# hat.net
KiCad netlist of a schematic drawn in EAGLE
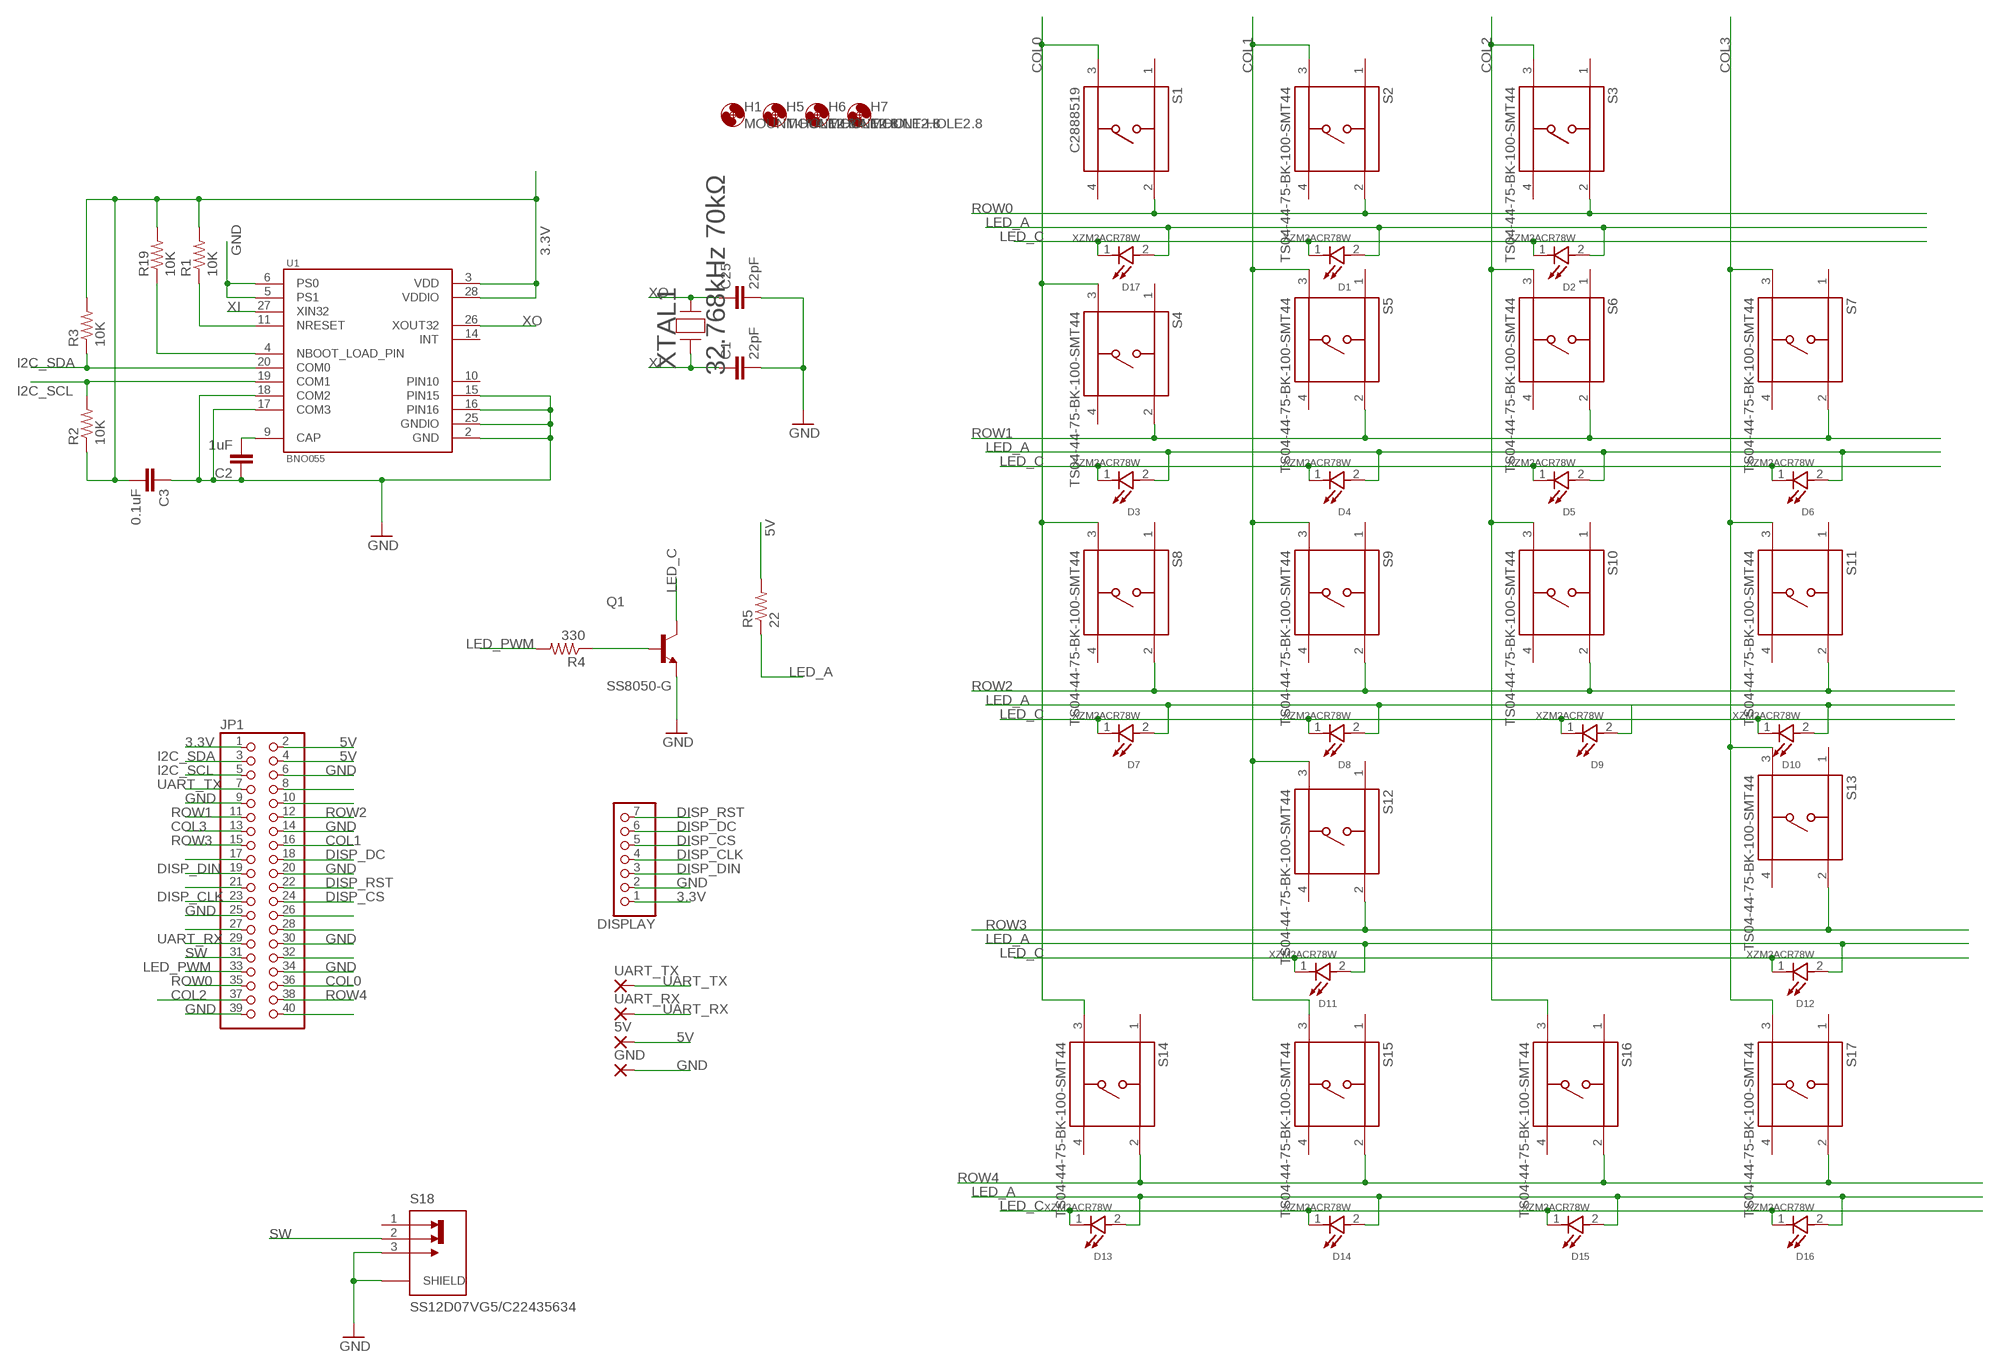
[diagram p0: schematic, sheet 1]

(export (version "E")
  (design (tool "Eeschema 10.0.6"))
  (components
    (comp (ref "5V")
      (value "SMD2")
      (footprint "eagle-import:SMD1,27-2,54")
      (libsource (lib "eagle-import") (part "SMD2"))
    )
    (comp (ref "C1")
      (value "22pF")
      (footprint "eagle-import:CAP_0603")
      (fields
        (field (name "DIGIKEY_PART_NUMBER") "399-7814-2-ND")
        (field (name "MANUFACTURER") "KEMET")
        (field (name "MPN") "C0603C100C5GACTU")
        (field (name "CREATED_BY") "PCBLayout.com")
      )
      (libsource (lib "eagle-import") (part "C0603C100C5GACTU"))
    )
    (comp (ref "C2")
      (value "1uF")
      (footprint "eagle-import:CAP_0603")
      (fields
        (field (name "DIGIKEY_PART_NUMBER") "399-7814-2-ND")
        (field (name "MANUFACTURER") "KEMET")
        (field (name "MPN") "C0603C100C5GACTU")
        (field (name "CREATED_BY") "PCBLayout.com")
      )
      (libsource (lib "eagle-import") (part "C0603C100C5GACTU"))
    )
    (comp (ref "C3")
      (value "0.1uF")
      (footprint "eagle-import:CAP_0603")
      (fields
        (field (name "DIGIKEY_PART_NUMBER") "399-7814-2-ND")
        (field (name "MANUFACTURER") "KEMET")
        (field (name "MPN") "C0603C100C5GACTU")
        (field (name "CREATED_BY") "PCBLayout.com")
      )
      (libsource (lib "eagle-import") (part "C0603C100C5GACTU"))
    )
    (comp (ref "C25")
      (value "22pF")
      (footprint "eagle-import:CAP_0603")
      (fields
        (field (name "DIGIKEY_PART_NUMBER") "399-7814-2-ND")
        (field (name "MANUFACTURER") "KEMET")
        (field (name "MPN") "C0603C100C5GACTU")
        (field (name "CREATED_BY") "PCBLayout.com")
      )
      (libsource (lib "eagle-import") (part "C0603C100C5GACTU"))
    )
    (comp (ref "D1")
      (value "XZM2ACR78W")
      (footprint "eagle-import:LED_XZM2ACR78W")
      (fields (field (name "MF") "SunLED"))
      (libsource (lib "eagle-import") (part "XZM2ACR78W"))
    )
    (comp (ref "D2")
      (value "XZM2ACR78W")
      (footprint "eagle-import:LED_XZM2ACR78W")
      (fields (field (name "MF") "SunLED"))
      (libsource (lib "eagle-import") (part "XZM2ACR78W"))
    )
    (comp (ref "D3")
      (value "XZM2ACR78W")
      (footprint "eagle-import:LED_XZM2ACR78W")
      (fields (field (name "MF") "SunLED"))
      (libsource (lib "eagle-import") (part "XZM2ACR78W"))
    )
    (comp (ref "D4")
      (value "XZM2ACR78W")
      (footprint "eagle-import:LED_XZM2ACR78W")
      (fields (field (name "MF") "SunLED"))
      (libsource (lib "eagle-import") (part "XZM2ACR78W"))
    )
    (comp (ref "D5")
      (value "XZM2ACR78W")
      (footprint "eagle-import:LED_XZM2ACR78W")
      (fields (field (name "MF") "SunLED"))
      (libsource (lib "eagle-import") (part "XZM2ACR78W"))
    )
    (comp (ref "D6")
      (value "XZM2ACR78W")
      (footprint "eagle-import:LED_XZM2ACR78W")
      (fields (field (name "MF") "SunLED"))
      (libsource (lib "eagle-import") (part "XZM2ACR78W"))
    )
    (comp (ref "D7")
      (value "XZM2ACR78W")
      (footprint "eagle-import:LED_XZM2ACR78W")
      (fields (field (name "MF") "SunLED"))
      (libsource (lib "eagle-import") (part "XZM2ACR78W"))
    )
    (comp (ref "D8")
      (value "XZM2ACR78W")
      (footprint "eagle-import:LED_XZM2ACR78W")
      (fields (field (name "MF") "SunLED"))
      (libsource (lib "eagle-import") (part "XZM2ACR78W"))
    )
    (comp (ref "D9")
      (value "XZM2ACR78W")
      (footprint "eagle-import:LED_XZM2ACR78W")
      (fields (field (name "MF") "SunLED"))
      (libsource (lib "eagle-import") (part "XZM2ACR78W"))
    )
    (comp (ref "D10")
      (value "XZM2ACR78W")
      (footprint "eagle-import:LED_XZM2ACR78W")
      (fields (field (name "MF") "SunLED"))
      (libsource (lib "eagle-import") (part "XZM2ACR78W"))
    )
    (comp (ref "D11")
      (value "XZM2ACR78W")
      (footprint "eagle-import:LED_XZM2ACR78W")
      (fields (field (name "MF") "SunLED"))
      (libsource (lib "eagle-import") (part "XZM2ACR78W"))
    )
    (comp (ref "D12")
      (value "XZM2ACR78W")
      (footprint "eagle-import:LED_XZM2ACR78W")
      (fields (field (name "MF") "SunLED"))
      (libsource (lib "eagle-import") (part "XZM2ACR78W"))
    )
    (comp (ref "D13")
      (value "XZM2ACR78W")
      (footprint "eagle-import:LED_XZM2ACR78W")
      (fields (field (name "MF") "SunLED"))
      (libsource (lib "eagle-import") (part "XZM2ACR78W"))
    )
    (comp (ref "D14")
      (value "XZM2ACR78W")
      (footprint "eagle-import:LED_XZM2ACR78W")
      (fields (field (name "MF") "SunLED"))
      (libsource (lib "eagle-import") (part "XZM2ACR78W"))
    )
    (comp (ref "D15")
      (value "XZM2ACR78W")
      (footprint "eagle-import:LED_XZM2ACR78W")
      (fields (field (name "MF") "SunLED"))
      (libsource (lib "eagle-import") (part "XZM2ACR78W"))
    )
    (comp (ref "D16")
      (value "XZM2ACR78W")
      (footprint "eagle-import:LED_XZM2ACR78W")
      (fields (field (name "MF") "SunLED"))
      (libsource (lib "eagle-import") (part "XZM2ACR78W"))
    )
    (comp (ref "D17")
      (value "XZM2ACR78W")
      (footprint "eagle-import:LED_XZM2ACR78W")
      (fields (field (name "MF") "SunLED"))
      (libsource (lib "eagle-import") (part "XZM2ACR78W"))
    )
    (comp (ref "DISPLAY")
      (value "PINHD-1X7")
      (footprint "eagle-import:1X07")
      (libsource (lib "eagle-import") (part "PINHD-1X7"))
    )
    (comp (ref "GND")
      (value "SMD2")
      (footprint "eagle-import:SMD1,27-2,54")
      (libsource (lib "eagle-import") (part "SMD2"))
    )
    (comp (ref "H1")
      (value "MOUNT-HOLE2.8")
      (footprint "eagle-import:2,8")
      (libsource (lib "eagle-import") (part "MOUNT-HOLE2.8"))
    )
    (comp (ref "H5")
      (value "MOUNT-HOLE2.8")
      (footprint "eagle-import:2,8")
      (libsource (lib "eagle-import") (part "MOUNT-HOLE2.8"))
    )
    (comp (ref "H6")
      (value "MOUNT-HOLE2.8")
      (footprint "eagle-import:2,8")
      (libsource (lib "eagle-import") (part "MOUNT-HOLE2.8"))
    )
    (comp (ref "H7")
      (value "MOUNT-HOLE2.8")
      (footprint "eagle-import:2,8")
      (libsource (lib "eagle-import") (part "MOUNT-HOLE2.8"))
    )
    (comp (ref "JP1")
      (value "PINHD-2X20")
      (footprint "eagle-import:2X20")
      (libsource (lib "eagle-import") (part "PINHD-2X20"))
    )
    (comp (ref "Q1")
      (value "SS8050-G")
      (footprint "eagle-import:TRANS_SS8050-G")
      (fields (field (name "MF") "Comchip Technology"))
      (libsource (lib "eagle-import") (part "SS8050-G"))
    )
    (comp (ref "R1")
      (value "10K")
      (footprint "eagle-import:RES_0603")
      (fields
        (field (name "DIGIKEY_PART_NUMBER") "311-0.0GRTR-ND")
        (field (name "MANUFACTURER") "Yageo")
        (field (name "MPN") "RC0603JR-070RL")
        (field (name "CREATED_BY") "PCBLayout.com")
      )
      (libsource (lib "eagle-import") (part "RC0603JR-070RL"))
    )
    (comp (ref "R2")
      (value "10K")
      (footprint "eagle-import:RES_0603")
      (fields
        (field (name "DIGIKEY_PART_NUMBER") "311-0.0GRTR-ND")
        (field (name "MANUFACTURER") "Yageo")
        (field (name "MPN") "RC0603JR-070RL")
        (field (name "CREATED_BY") "PCBLayout.com")
      )
      (libsource (lib "eagle-import") (part "RC0603JR-070RL"))
    )
    (comp (ref "R3")
      (value "10K")
      (footprint "eagle-import:RES_0603")
      (fields
        (field (name "DIGIKEY_PART_NUMBER") "311-0.0GRTR-ND")
        (field (name "MANUFACTURER") "Yageo")
        (field (name "MPN") "RC0603JR-070RL")
        (field (name "CREATED_BY") "PCBLayout.com")
      )
      (libsource (lib "eagle-import") (part "RC0603JR-070RL"))
    )
    (comp (ref "R4")
      (value "330")
      (footprint "eagle-import:RES_0603")
      (fields
        (field (name "DIGIKEY_PART_NUMBER") "311-0.0GRTR-ND")
        (field (name "MANUFACTURER") "Yageo")
        (field (name "MPN") "RC0603JR-070RL")
        (field (name "CREATED_BY") "PCBLayout.com")
      )
      (libsource (lib "eagle-import") (part "RC0603JR-070RL"))
    )
    (comp (ref "R5")
      (value "22")
      (footprint "eagle-import:RES_0603")
      (fields
        (field (name "DIGIKEY_PART_NUMBER") "311-0.0GRTR-ND")
        (field (name "MANUFACTURER") "Yageo")
        (field (name "MPN") "RC0603JR-070RL")
        (field (name "CREATED_BY") "PCBLayout.com")
      )
      (libsource (lib "eagle-import") (part "RC0603JR-070RL"))
    )
    (comp (ref "R19")
      (value "10K")
      (footprint "eagle-import:RES_0603")
      (fields
        (field (name "DIGIKEY_PART_NUMBER") "311-0.0GRTR-ND")
        (field (name "MANUFACTURER") "Yageo")
        (field (name "MPN") "RC0603JR-070RL")
        (field (name "CREATED_BY") "PCBLayout.com")
      )
      (libsource (lib "eagle-import") (part "RC0603JR-070RL"))
    )
    (comp (ref "S1")
      (value "C2888519")
      (footprint "eagle-import:SW_TS04-44")
      (libsource (lib "eagle-import") (part "TS04-44-75-BK-100-SMT44"))
    )
    (comp (ref "S2")
      (value "TS04-44-75-BK-100-SMT44")
      (footprint "eagle-import:SW_TS04-44")
      (libsource (lib "eagle-import") (part "TS04-44-75-BK-100-SMT44"))
    )
    (comp (ref "S3")
      (value "TS04-44-75-BK-100-SMT44")
      (footprint "eagle-import:SW_TS04-44")
      (libsource (lib "eagle-import") (part "TS04-44-75-BK-100-SMT44"))
    )
    (comp (ref "S4")
      (value "TS04-44-75-BK-100-SMT44")
      (footprint "eagle-import:SW_TS04-44")
      (libsource (lib "eagle-import") (part "TS04-44-75-BK-100-SMT44"))
    )
    (comp (ref "S5")
      (value "TS04-44-75-BK-100-SMT44")
      (footprint "eagle-import:SW_TS04-44")
      (libsource (lib "eagle-import") (part "TS04-44-75-BK-100-SMT44"))
    )
    (comp (ref "S6")
      (value "TS04-44-75-BK-100-SMT44")
      (footprint "eagle-import:SW_TS04-44")
      (libsource (lib "eagle-import") (part "TS04-44-75-BK-100-SMT44"))
    )
    (comp (ref "S7")
      (value "TS04-44-75-BK-100-SMT44")
      (footprint "eagle-import:SW_TS04-44")
      (libsource (lib "eagle-import") (part "TS04-44-75-BK-100-SMT44"))
    )
    (comp (ref "S8")
      (value "TS04-44-75-BK-100-SMT44")
      (footprint "eagle-import:SW_TS04-44")
      (libsource (lib "eagle-import") (part "TS04-44-75-BK-100-SMT44"))
    )
    (comp (ref "S9")
      (value "TS04-44-75-BK-100-SMT44")
      (footprint "eagle-import:SW_TS04-44")
      (libsource (lib "eagle-import") (part "TS04-44-75-BK-100-SMT44"))
    )
    (comp (ref "S10")
      (value "TS04-44-75-BK-100-SMT44")
      (footprint "eagle-import:SW_TS04-44")
      (libsource (lib "eagle-import") (part "TS04-44-75-BK-100-SMT44"))
    )
    (comp (ref "S11")
      (value "TS04-44-75-BK-100-SMT44")
      (footprint "eagle-import:SW_TS04-44")
      (libsource (lib "eagle-import") (part "TS04-44-75-BK-100-SMT44"))
    )
    (comp (ref "S12")
      (value "TS04-44-75-BK-100-SMT44")
      (footprint "eagle-import:SW_TS04-44")
      (libsource (lib "eagle-import") (part "TS04-44-75-BK-100-SMT44"))
    )
    (comp (ref "S13")
      (value "TS04-44-75-BK-100-SMT44")
      (footprint "eagle-import:SW_TS04-44")
      (libsource (lib "eagle-import") (part "TS04-44-75-BK-100-SMT44"))
    )
    (comp (ref "S14")
      (value "TS04-44-75-BK-100-SMT44")
      (footprint "eagle-import:SW_TS04-44")
      (libsource (lib "eagle-import") (part "TS04-44-75-BK-100-SMT44"))
    )
    (comp (ref "S15")
      (value "TS04-44-75-BK-100-SMT44")
      (footprint "eagle-import:SW_TS04-44")
      (libsource (lib "eagle-import") (part "TS04-44-75-BK-100-SMT44"))
    )
    (comp (ref "S16")
      (value "TS04-44-75-BK-100-SMT44")
      (footprint "eagle-import:SW_TS04-44")
      (libsource (lib "eagle-import") (part "TS04-44-75-BK-100-SMT44"))
    )
    (comp (ref "S17")
      (value "TS04-44-75-BK-100-SMT44")
      (footprint "eagle-import:SW_TS04-44")
      (libsource (lib "eagle-import") (part "TS04-44-75-BK-100-SMT44"))
    )
    (comp (ref "S18")
      (value "SS12D07VG5/C22435634")
      (footprint "eagle-import:SW_SS12D07VG4")
      (fields (field (name "MF") "Shouhan") (field (name "MP") "SS12D07VG4"))
      (libsource (lib "eagle-import") (part "SS12D07VG4"))
    )
    (comp (ref "U1")
      (value "BNO055")
      (footprint "eagle-import:LGA28R50P4X10_380X520X100")
      (fields (field (name "MF") "Bosch"))
      (libsource (lib "eagle-import") (part "BNO055"))
    )
    (comp (ref "UART_RX")
      (value "SMD2")
      (footprint "eagle-import:SMD1,27-2,54")
      (libsource (lib "eagle-import") (part "SMD2"))
    )
    (comp (ref "UART_TX")
      (value "SMD2")
      (footprint "eagle-import:SMD1,27-2,54")
      (libsource (lib "eagle-import") (part "SMD2"))
    )
    (comp (ref "XTAL1")
      (value "32.768kHz 70kΩ")
      (footprint "eagle-import:XTAL_FC-135_EPS")
      (fields (field (name "MF") "EPSON") (field (name "MP") "Q13FC1350000400"))
      (libsource (lib "eagle-import") (part "Q13FC1350000400"))
    )
  )
  (nets
    (net (code "1") (name "/3.3V") (class "Default")
      (node (ref "C3") (pin "2") (pinfunction "2_2") (pintype "passive"))
      (node (ref "DISPLAY") (pin "1") (pinfunction "1_1") (pintype "passive"))
      (node (ref "JP1") (pin "1") (pinfunction "1_1") (pintype "passive"))
      (node (ref "R1") (pin "2") (pinfunction "2_2") (pintype "passive"))
      (node (ref "R19") (pin "2") (pinfunction "2_2") (pintype "passive"))
      (node (ref "R2") (pin "1") (pinfunction "1_1") (pintype "passive"))
      (node (ref "R3") (pin "2") (pinfunction "2_2") (pintype "passive"))
      (node (ref "U1") (pin "28") (pinfunction "VDDIO_28") (pintype "power_in"))
      (node (ref "U1") (pin "3") (pinfunction "VDD_3") (pintype "power_in"))
    )
    (net (code "2") (name "/5V") (class "Default")
      (node (ref "5V") (pin "1") (pinfunction "P_1") (pintype "passive"))
      (node (ref "JP1") (pin "2") (pinfunction "2_2") (pintype "passive"))
      (node (ref "JP1") (pin "4") (pinfunction "4_4") (pintype "passive"))
      (node (ref "R5") (pin "2") (pinfunction "2_2") (pintype "passive"))
    )
    (net (code "3") (name "/COL0") (class "Default")
      (node (ref "JP1") (pin "36") (pinfunction "36_36") (pintype "passive"))
      (node (ref "S1") (pin "3") (pinfunction "2_3") (pintype "passive"))
      (node (ref "S14") (pin "3") (pinfunction "2_3") (pintype "passive"))
      (node (ref "S4") (pin "3") (pinfunction "2_3") (pintype "passive"))
      (node (ref "S8") (pin "3") (pinfunction "2_3") (pintype "passive"))
    )
    (net (code "4") (name "/COL1") (class "Default")
      (node (ref "JP1") (pin "16") (pinfunction "16_16") (pintype "passive"))
      (node (ref "S12") (pin "3") (pinfunction "2_3") (pintype "passive"))
      (node (ref "S15") (pin "3") (pinfunction "2_3") (pintype "passive"))
      (node (ref "S2") (pin "3") (pinfunction "2_3") (pintype "passive"))
      (node (ref "S5") (pin "3") (pinfunction "2_3") (pintype "passive"))
      (node (ref "S9") (pin "3") (pinfunction "2_3") (pintype "passive"))
    )
    (net (code "5") (name "/COL2") (class "Default")
      (node (ref "JP1") (pin "37") (pinfunction "37_37") (pintype "passive"))
      (node (ref "S10") (pin "3") (pinfunction "2_3") (pintype "passive"))
      (node (ref "S16") (pin "3") (pinfunction "2_3") (pintype "passive"))
      (node (ref "S3") (pin "3") (pinfunction "2_3") (pintype "passive"))
      (node (ref "S6") (pin "3") (pinfunction "2_3") (pintype "passive"))
    )
    (net (code "6") (name "/COL3") (class "Default")
      (node (ref "JP1") (pin "13") (pinfunction "13_13") (pintype "passive"))
      (node (ref "S11") (pin "3") (pinfunction "2_3") (pintype "passive"))
      (node (ref "S13") (pin "3") (pinfunction "2_3") (pintype "passive"))
      (node (ref "S17") (pin "3") (pinfunction "2_3") (pintype "passive"))
      (node (ref "S7") (pin "3") (pinfunction "2_3") (pintype "passive"))
    )
    (net (code "7") (name "/DISP_CLK") (class "Default")
      (node (ref "DISPLAY") (pin "4") (pinfunction "4_4") (pintype "passive"))
      (node (ref "JP1") (pin "23") (pinfunction "23_23") (pintype "passive"))
    )
    (net (code "8") (name "/DISP_CS") (class "Default")
      (node (ref "DISPLAY") (pin "5") (pinfunction "5_5") (pintype "passive"))
      (node (ref "JP1") (pin "24") (pinfunction "24_24") (pintype "passive"))
    )
    (net (code "9") (name "/DISP_DC") (class "Default")
      (node (ref "DISPLAY") (pin "6") (pinfunction "6_6") (pintype "passive"))
      (node (ref "JP1") (pin "18") (pinfunction "18_18") (pintype "passive"))
    )
    (net (code "10") (name "/DISP_DIN") (class "Default")
      (node (ref "DISPLAY") (pin "3") (pinfunction "3_3") (pintype "passive"))
      (node (ref "JP1") (pin "19") (pinfunction "19_19") (pintype "passive"))
    )
    (net (code "11") (name "/DISP_RST") (class "Default")
      (node (ref "DISPLAY") (pin "7") (pinfunction "7_7") (pintype "passive"))
      (node (ref "JP1") (pin "22") (pinfunction "22_22") (pintype "passive"))
    )
    (net (code "12") (name "/I2C_SCL") (class "Default")
      (node (ref "JP1") (pin "5") (pinfunction "5_5") (pintype "passive"))
      (node (ref "R2") (pin "2") (pinfunction "2_2") (pintype "passive"))
      (node (ref "U1") (pin "19") (pinfunction "COM1_19") (pintype "bidirectional"))
    )
    (net (code "13") (name "/I2C_SDA") (class "Default")
      (node (ref "JP1") (pin "3") (pinfunction "3_3") (pintype "passive"))
      (node (ref "R3") (pin "1") (pinfunction "1_1") (pintype "passive"))
      (node (ref "U1") (pin "20") (pinfunction "COM0_20") (pintype "bidirectional"))
    )
    (net (code "14") (name "/LED_A") (class "Default")
      (node (ref "D1") (pin "2") (pinfunction "A_2") (pintype "passive"))
      (node (ref "D10") (pin "2") (pinfunction "A_2") (pintype "passive"))
      (node (ref "D11") (pin "2") (pinfunction "A_2") (pintype "passive"))
      (node (ref "D12") (pin "2") (pinfunction "A_2") (pintype "passive"))
      (node (ref "D13") (pin "2") (pinfunction "A_2") (pintype "passive"))
      (node (ref "D14") (pin "2") (pinfunction "A_2") (pintype "passive"))
      (node (ref "D15") (pin "2") (pinfunction "A_2") (pintype "passive"))
      (node (ref "D16") (pin "2") (pinfunction "A_2") (pintype "passive"))
      (node (ref "D17") (pin "2") (pinfunction "A_2") (pintype "passive"))
      (node (ref "D2") (pin "2") (pinfunction "A_2") (pintype "passive"))
      (node (ref "D3") (pin "2") (pinfunction "A_2") (pintype "passive"))
      (node (ref "D4") (pin "2") (pinfunction "A_2") (pintype "passive"))
      (node (ref "D5") (pin "2") (pinfunction "A_2") (pintype "passive"))
      (node (ref "D6") (pin "2") (pinfunction "A_2") (pintype "passive"))
      (node (ref "D7") (pin "2") (pinfunction "A_2") (pintype "passive"))
      (node (ref "D8") (pin "2") (pinfunction "A_2") (pintype "passive"))
      (node (ref "D9") (pin "2") (pinfunction "A_2") (pintype "passive"))
      (node (ref "R5") (pin "1") (pinfunction "1_1") (pintype "passive"))
    )
    (net (code "15") (name "/LED_C") (class "Default")
      (node (ref "D1") (pin "1") (pinfunction "C_1") (pintype "passive"))
      (node (ref "D10") (pin "1") (pinfunction "C_1") (pintype "passive"))
      (node (ref "D11") (pin "1") (pinfunction "C_1") (pintype "passive"))
      (node (ref "D12") (pin "1") (pinfunction "C_1") (pintype "passive"))
      (node (ref "D13") (pin "1") (pinfunction "C_1") (pintype "passive"))
      (node (ref "D14") (pin "1") (pinfunction "C_1") (pintype "passive"))
      (node (ref "D15") (pin "1") (pinfunction "C_1") (pintype "passive"))
      (node (ref "D16") (pin "1") (pinfunction "C_1") (pintype "passive"))
      (node (ref "D17") (pin "1") (pinfunction "C_1") (pintype "passive"))
      (node (ref "D2") (pin "1") (pinfunction "C_1") (pintype "passive"))
      (node (ref "D3") (pin "1") (pinfunction "C_1") (pintype "passive"))
      (node (ref "D4") (pin "1") (pinfunction "C_1") (pintype "passive"))
      (node (ref "D5") (pin "1") (pinfunction "C_1") (pintype "passive"))
      (node (ref "D6") (pin "1") (pinfunction "C_1") (pintype "passive"))
      (node (ref "D7") (pin "1") (pinfunction "C_1") (pintype "passive"))
      (node (ref "D8") (pin "1") (pinfunction "C_1") (pintype "passive"))
      (node (ref "D9") (pin "1") (pinfunction "C_1") (pintype "passive"))
      (node (ref "Q1") (pin "3") (pinfunction "C_3") (pintype "passive"))
    )
    (net (code "16") (name "/LED_PWM") (class "Default")
      (node (ref "JP1") (pin "33") (pinfunction "33_33") (pintype "passive"))
      (node (ref "R4") (pin "2") (pinfunction "2_2") (pintype "passive"))
    )
    (net (code "17") (name "/PIN10") (class "Default")
      (node (ref "U1") (pin "10") (pinfunction "PIN10_10") (pintype "power_in"))
    )
    (net (code "18") (name "/ROW0") (class "Default")
      (node (ref "JP1") (pin "35") (pinfunction "35_35") (pintype "passive"))
      (node (ref "S1") (pin "2") (pinfunction "3_2") (pintype "passive"))
      (node (ref "S2") (pin "2") (pinfunction "3_2") (pintype "passive"))
      (node (ref "S3") (pin "2") (pinfunction "3_2") (pintype "passive"))
    )
    (net (code "19") (name "/ROW1") (class "Default")
      (node (ref "JP1") (pin "11") (pinfunction "11_11") (pintype "passive"))
      (node (ref "S4") (pin "2") (pinfunction "3_2") (pintype "passive"))
      (node (ref "S5") (pin "2") (pinfunction "3_2") (pintype "passive"))
      (node (ref "S6") (pin "2") (pinfunction "3_2") (pintype "passive"))
      (node (ref "S7") (pin "2") (pinfunction "3_2") (pintype "passive"))
    )
    (net (code "20") (name "/ROW2") (class "Default")
      (node (ref "JP1") (pin "12") (pinfunction "12_12") (pintype "passive"))
      (node (ref "S10") (pin "2") (pinfunction "3_2") (pintype "passive"))
      (node (ref "S11") (pin "2") (pinfunction "3_2") (pintype "passive"))
      (node (ref "S8") (pin "2") (pinfunction "3_2") (pintype "passive"))
      (node (ref "S9") (pin "2") (pinfunction "3_2") (pintype "passive"))
    )
    (net (code "21") (name "/ROW3") (class "Default")
      (node (ref "JP1") (pin "15") (pinfunction "15_15") (pintype "passive"))
      (node (ref "S12") (pin "2") (pinfunction "3_2") (pintype "passive"))
      (node (ref "S13") (pin "2") (pinfunction "3_2") (pintype "passive"))
    )
    (net (code "22") (name "/ROW4") (class "Default")
      (node (ref "JP1") (pin "38") (pinfunction "38_38") (pintype "passive"))
      (node (ref "S14") (pin "2") (pinfunction "3_2") (pintype "passive"))
      (node (ref "S15") (pin "2") (pinfunction "3_2") (pintype "passive"))
      (node (ref "S16") (pin "2") (pinfunction "3_2") (pintype "passive"))
      (node (ref "S17") (pin "2") (pinfunction "3_2") (pintype "passive"))
    )
    (net (code "23") (name "/SW") (class "Default")
      (node (ref "JP1") (pin "31") (pinfunction "31_31") (pintype "passive"))
      (node (ref "S18") (pin "2") (pinfunction "2_2") (pintype "passive"))
    )
    (net (code "24") (name "/UART_RX") (class "Default")
      (node (ref "JP1") (pin "29") (pinfunction "29_29") (pintype "passive"))
      (node (ref "UART_RX") (pin "1") (pinfunction "P_1") (pintype "passive"))
    )
    (net (code "25") (name "/UART_TX") (class "Default")
      (node (ref "JP1") (pin "7") (pinfunction "7_7") (pintype "passive"))
      (node (ref "UART_TX") (pin "1") (pinfunction "P_1") (pintype "passive"))
    )
    (net (code "26") (name "/XI") (class "Default")
      (node (ref "C1") (pin "1") (pinfunction "1_1") (pintype "passive"))
      (node (ref "U1") (pin "27") (pinfunction "XIN32_27") (pintype "input"))
      (node (ref "XTAL1") (pin "1") (pinfunction "1_1") (pintype "passive"))
    )
    (net (code "27") (name "/XO") (class "Default")
      (node (ref "C25") (pin "1") (pinfunction "1_1") (pintype "passive"))
      (node (ref "U1") (pin "26") (pinfunction "XOUT32_26") (pintype "output"))
      (node (ref "XTAL1") (pin "2") (pinfunction "2_2") (pintype "passive"))
    )
    (net (code "28") (name "GND") (class "Default")
      (node (ref "C1") (pin "2") (pinfunction "2_2") (pintype "passive"))
      (node (ref "C2") (pin "1") (pinfunction "1_1") (pintype "passive"))
      (node (ref "C25") (pin "2") (pinfunction "2_2") (pintype "passive"))
      (node (ref "C3") (pin "1") (pinfunction "1_1") (pintype "passive"))
      (node (ref "DISPLAY") (pin "2") (pinfunction "2_2") (pintype "passive"))
      (node (ref "GND") (pin "1") (pinfunction "P_1") (pintype "passive"))
      (node (ref "JP1") (pin "14") (pinfunction "14_14") (pintype "passive"))
      (node (ref "JP1") (pin "20") (pinfunction "20_20") (pintype "passive"))
      (node (ref "JP1") (pin "25") (pinfunction "25_25") (pintype "passive"))
      (node (ref "JP1") (pin "30") (pinfunction "30_30") (pintype "passive"))
      (node (ref "JP1") (pin "34") (pinfunction "34_34") (pintype "passive"))
      (node (ref "JP1") (pin "39") (pinfunction "39_39") (pintype "passive"))
      (node (ref "JP1") (pin "6") (pinfunction "6_6") (pintype "passive"))
      (node (ref "JP1") (pin "9") (pinfunction "9_9") (pintype "passive"))
      (node (ref "Q1") (pin "2") (pinfunction "E_2") (pintype "passive"))
      (node (ref "S18") (pin "3") (pinfunction "3_3") (pintype "passive"))
      (node (ref "S18") (pin "S1") (pinfunction "SHIELD_S1") (pintype "passive"))
      (node (ref "S18") (pin "S2") (pinfunction "SHIELD_S2") (pintype "passive"))
      (node (ref "U1") (pin "15") (pinfunction "PIN15_15") (pintype "power_in"))
      (node (ref "U1") (pin "16") (pinfunction "PIN16_16") (pintype "power_in"))
      (node (ref "U1") (pin "17") (pinfunction "COM3_17") (pintype "bidirectional"))
      (node (ref "U1") (pin "18") (pinfunction "COM2_18") (pintype "bidirectional"))
      (node (ref "U1") (pin "2") (pinfunction "GND_2") (pintype "power_in"))
      (node (ref "U1") (pin "25") (pinfunction "GNDIO_25") (pintype "power_in"))
      (node (ref "U1") (pin "5") (pinfunction "PS1_5") (pintype "input"))
      (node (ref "U1") (pin "6") (pinfunction "PS0_6") (pintype "input"))
    )
    (net (code "29") (name "Net-(Q1-B)") (class "Default")
      (node (ref "Q1") (pin "1") (pinfunction "B_1") (pintype "passive"))
      (node (ref "R4") (pin "1") (pinfunction "1_1") (pintype "passive"))
    )
    (net (code "30") (name "Net-(U1-CAP)") (class "Default")
      (node (ref "C2") (pin "2") (pinfunction "2_2") (pintype "passive"))
      (node (ref "U1") (pin "9") (pinfunction "CAP_9") (pintype "passive"))
    )
    (net (code "31") (name "Net-(U1-NBOOT_LOAD_PIN)") (class "Default")
      (node (ref "R19") (pin "1") (pinfunction "1_1") (pintype "passive"))
      (node (ref "U1") (pin "4") (pinfunction "NBOOT_LOAD_PIN_4") (pintype "bidirectional"))
    )
    (net (code "32") (name "Net-(U1-NRESET)") (class "Default")
      (node (ref "R1") (pin "1") (pinfunction "1_1") (pintype "passive"))
      (node (ref "U1") (pin "11") (pinfunction "NRESET_11") (pintype "input"))
    )
    (net (code "33") (name "unconnected-(JP1-Pad8)") (class "Default")
      (node (ref "JP1") (pin "8") (pinfunction "8_8") (pintype "passive"))
    )
    (net (code "34") (name "unconnected-(JP1-Pad10)") (class "Default")
      (node (ref "JP1") (pin "10") (pinfunction "10_10") (pintype "passive"))
    )
    (net (code "35") (name "unconnected-(JP1-Pad17)") (class "Default")
      (node (ref "JP1") (pin "17") (pinfunction "17_17") (pintype "passive"))
    )
    (net (code "36") (name "unconnected-(JP1-Pad21)") (class "Default")
      (node (ref "JP1") (pin "21") (pinfunction "21_21") (pintype "passive"))
    )
    (net (code "37") (name "unconnected-(JP1-Pad26)") (class "Default")
      (node (ref "JP1") (pin "26") (pinfunction "26_26") (pintype "passive"))
    )
    (net (code "38") (name "unconnected-(JP1-Pad27)") (class "Default")
      (node (ref "JP1") (pin "27") (pinfunction "27_27") (pintype "passive"))
    )
    (net (code "39") (name "unconnected-(JP1-Pad28)") (class "Default")
      (node (ref "JP1") (pin "28") (pinfunction "28_28") (pintype "passive"))
    )
    (net (code "40") (name "unconnected-(JP1-Pad32)") (class "Default")
      (node (ref "JP1") (pin "32") (pinfunction "32_32") (pintype "passive"))
    )
    (net (code "41") (name "unconnected-(JP1-Pad40)") (class "Default")
      (node (ref "JP1") (pin "40") (pinfunction "40_40") (pintype "passive"))
    )
    (net (code "42") (name "unconnected-(S1-Pad1)") (class "Default")
      (node (ref "S1") (pin "1") (pinfunction "1_1") (pintype "passive"))
    )
    (net (code "43") (name "unconnected-(S1-Pad4)") (class "Default")
      (node (ref "S1") (pin "4") (pinfunction "4_4") (pintype "passive"))
    )
    (net (code "44") (name "unconnected-(S2-Pad1)") (class "Default")
      (node (ref "S2") (pin "1") (pinfunction "1_1") (pintype "passive"))
    )
    (net (code "45") (name "unconnected-(S2-Pad4)") (class "Default")
      (node (ref "S2") (pin "4") (pinfunction "4_4") (pintype "passive"))
    )
    (net (code "46") (name "unconnected-(S3-Pad1)") (class "Default")
      (node (ref "S3") (pin "1") (pinfunction "1_1") (pintype "passive"))
    )
    (net (code "47") (name "unconnected-(S3-Pad4)") (class "Default")
      (node (ref "S3") (pin "4") (pinfunction "4_4") (pintype "passive"))
    )
    (net (code "48") (name "unconnected-(S4-Pad1)") (class "Default")
      (node (ref "S4") (pin "1") (pinfunction "1_1") (pintype "passive"))
    )
    (net (code "49") (name "unconnected-(S4-Pad4)") (class "Default")
      (node (ref "S4") (pin "4") (pinfunction "4_4") (pintype "passive"))
    )
    (net (code "50") (name "unconnected-(S5-Pad1)") (class "Default")
      (node (ref "S5") (pin "1") (pinfunction "1_1") (pintype "passive"))
    )
    (net (code "51") (name "unconnected-(S5-Pad4)") (class "Default")
      (node (ref "S5") (pin "4") (pinfunction "4_4") (pintype "passive"))
    )
    (net (code "52") (name "unconnected-(S6-Pad1)") (class "Default")
      (node (ref "S6") (pin "1") (pinfunction "1_1") (pintype "passive"))
    )
    (net (code "53") (name "unconnected-(S6-Pad4)") (class "Default")
      (node (ref "S6") (pin "4") (pinfunction "4_4") (pintype "passive"))
    )
    (net (code "54") (name "unconnected-(S7-Pad1)") (class "Default")
      (node (ref "S7") (pin "1") (pinfunction "1_1") (pintype "passive"))
    )
    (net (code "55") (name "unconnected-(S7-Pad4)") (class "Default")
      (node (ref "S7") (pin "4") (pinfunction "4_4") (pintype "passive"))
    )
    (net (code "56") (name "unconnected-(S8-Pad1)") (class "Default")
      (node (ref "S8") (pin "1") (pinfunction "1_1") (pintype "passive"))
    )
    (net (code "57") (name "unconnected-(S8-Pad4)") (class "Default")
      (node (ref "S8") (pin "4") (pinfunction "4_4") (pintype "passive"))
    )
    (net (code "58") (name "unconnected-(S9-Pad1)") (class "Default")
      (node (ref "S9") (pin "1") (pinfunction "1_1") (pintype "passive"))
    )
    (net (code "59") (name "unconnected-(S9-Pad4)") (class "Default")
      (node (ref "S9") (pin "4") (pinfunction "4_4") (pintype "passive"))
    )
    (net (code "60") (name "unconnected-(S10-Pad1)") (class "Default")
      (node (ref "S10") (pin "1") (pinfunction "1_1") (pintype "passive"))
    )
    (net (code "61") (name "unconnected-(S10-Pad4)") (class "Default")
      (node (ref "S10") (pin "4") (pinfunction "4_4") (pintype "passive"))
    )
    (net (code "62") (name "unconnected-(S11-Pad1)") (class "Default")
      (node (ref "S11") (pin "1") (pinfunction "1_1") (pintype "passive"))
    )
    (net (code "63") (name "unconnected-(S11-Pad4)") (class "Default")
      (node (ref "S11") (pin "4") (pinfunction "4_4") (pintype "passive"))
    )
    (net (code "64") (name "unconnected-(S12-Pad1)") (class "Default")
      (node (ref "S12") (pin "1") (pinfunction "1_1") (pintype "passive"))
    )
    (net (code "65") (name "unconnected-(S12-Pad4)") (class "Default")
      (node (ref "S12") (pin "4") (pinfunction "4_4") (pintype "passive"))
    )
    (net (code "66") (name "unconnected-(S13-Pad1)") (class "Default")
      (node (ref "S13") (pin "1") (pinfunction "1_1") (pintype "passive"))
    )
    (net (code "67") (name "unconnected-(S13-Pad4)") (class "Default")
      (node (ref "S13") (pin "4") (pinfunction "4_4") (pintype "passive"))
    )
    (net (code "68") (name "unconnected-(S14-Pad1)") (class "Default")
      (node (ref "S14") (pin "1") (pinfunction "1_1") (pintype "passive"))
    )
    (net (code "69") (name "unconnected-(S14-Pad4)") (class "Default")
      (node (ref "S14") (pin "4") (pinfunction "4_4") (pintype "passive"))
    )
    (net (code "70") (name "unconnected-(S15-Pad1)") (class "Default")
      (node (ref "S15") (pin "1") (pinfunction "1_1") (pintype "passive"))
    )
    (net (code "71") (name "unconnected-(S15-Pad4)") (class "Default")
      (node (ref "S15") (pin "4") (pinfunction "4_4") (pintype "passive"))
    )
    (net (code "72") (name "unconnected-(S16-Pad1)") (class "Default")
      (node (ref "S16") (pin "1") (pinfunction "1_1") (pintype "passive"))
    )
    (net (code "73") (name "unconnected-(S16-Pad4)") (class "Default")
      (node (ref "S16") (pin "4") (pinfunction "4_4") (pintype "passive"))
    )
    (net (code "74") (name "unconnected-(S17-Pad1)") (class "Default")
      (node (ref "S17") (pin "1") (pinfunction "1_1") (pintype "passive"))
    )
    (net (code "75") (name "unconnected-(S17-Pad4)") (class "Default")
      (node (ref "S17") (pin "4") (pinfunction "4_4") (pintype "passive"))
    )
    (net (code "76") (name "unconnected-(S18-Pad1)") (class "Default")
      (node (ref "S18") (pin "1") (pinfunction "1_1") (pintype "passive"))
    )
    (net (code "77") (name "unconnected-(U1-INT-Pad14)") (class "Default")
      (node (ref "U1") (pin "14") (pinfunction "INT_14") (pintype "output"))
    )
  )
)
